# RELAY_5V_3_3V_LEVEL.net
KiCad netlist of a schematic drawn in Altium Designer
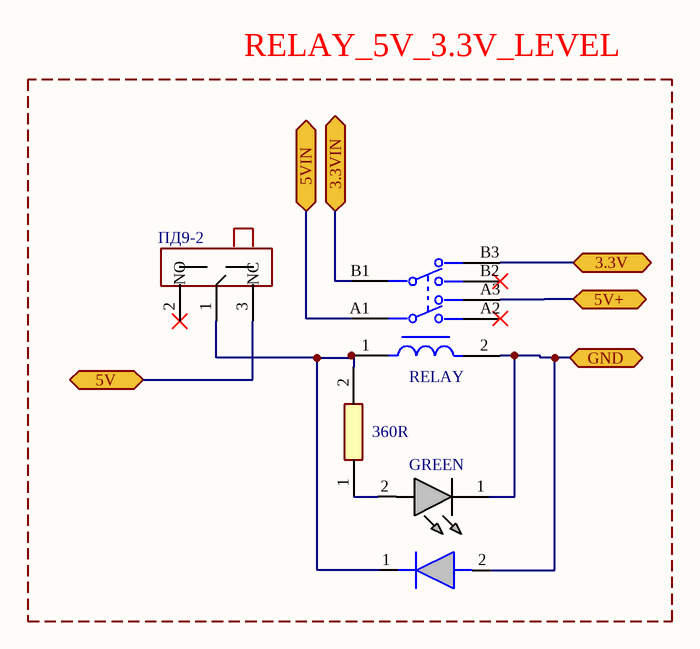
[diagram p0: RELAY_5V_3.3V_LEVEL.SchDoc]

(export (version "E")
  (design (tool "Eeschema 10.0.6"))
  (components
    (comp (ref "DIODRELE2")
      (value "DIOD0805")
      (footprint "DIOD0805")
      (description "1N4448WS-7-F")
      (libsource (lib "Components_Robots") (part "DIOD0805"))
    )
    (comp (ref "LEDRELE2")
      (value "GREEN")
      (footprint "LED0805")
      (description "LED-SMD0805")
      (libsource (lib "Components_Robots") (part "LED0805"))
    )
    (comp (ref "RELAY2")
      (value "RELAY")
      (footprint "RELAY-5V")
      (description "R2G2CH005")
      (libsource (lib "Components_Robots") (part "RELAY-5V"))
    )
    (comp (ref "RES_RELAY_2")
      (value "360R")
      (footprint "RES0805")
      (description "RES-SMD0805")
      (libsource (lib "Components_Robots") (part "RES0805"))
    )
    (comp (ref "ПД9-2RELE1")
      (value "ПД9-2")
      (footprint "ПД9-2")
      (libsource (lib "Components_Robots") (part "ПД9-2"))
    )
  )
  (nets
    (net (code "1") (name "/3.3V") (class "Default")
      (node (ref "RELAY2") (pin "B3") (pinfunction "22_B3") (pintype "passive"))
    )
    (net (code "2") (name "/3.3VIN") (class "Default")
      (node (ref "RELAY2") (pin "B1") (pinfunction "21_B1") (pintype "passive"))
    )
    (net (code "3") (name "/5V") (class "Default")
      (node (ref "ПД9-2RELE1") (pin "3") (pinfunction "NC_3") (pintype "passive"))
    )
    (net (code "4") (name "/5V+") (class "Default")
      (node (ref "RELAY2") (pin "A3") (pinfunction "12_A3") (pintype "passive"))
    )
    (net (code "5") (name "/5VIN") (class "Default")
      (node (ref "RELAY2") (pin "A1") (pinfunction "11_A1") (pintype "passive"))
    )
    (net (code "6") (name "/GND") (class "Default")
      (node (ref "DIODRELE2") (pin "2") (pinfunction "A_2") (pintype "passive"))
      (node (ref "LEDRELE2") (pin "1") (pinfunction "K_1") (pintype "passive"))
      (node (ref "RELAY2") (pin "2") (pinfunction "A2_2") (pintype "passive"))
    )
    (net (code "7") (name "Net-(DIODRELE2-K)") (class "Default")
      (node (ref "DIODRELE2") (pin "1") (pinfunction "K_1") (pintype "passive"))
      (node (ref "RELAY2") (pin "1") (pinfunction "A1_1") (pintype "passive"))
      (node (ref "RES_RELAY_2") (pin "2") (pinfunction "2_2") (pintype "passive"))
      (node (ref "ПД9-2RELE1") (pin "1") (pinfunction "COM_1") (pintype "passive"))
    )
    (net (code "8") (name "Net-(LEDRELE2-A)") (class "Default")
      (node (ref "LEDRELE2") (pin "2") (pinfunction "A_2") (pintype "passive"))
      (node (ref "RES_RELAY_2") (pin "1") (pinfunction "1_1") (pintype "passive"))
    )
    (net (code "9") (name "unconnected-(RELAY2-14-PadA2)") (class "Default")
      (node (ref "RELAY2") (pin "A2") (pinfunction "14_A2") (pintype "passive+no_connect"))
    )
    (net (code "10") (name "unconnected-(RELAY2-24-PadB2)") (class "Default")
      (node (ref "RELAY2") (pin "B2") (pinfunction "24_B2") (pintype "passive+no_connect"))
    )
    (net (code "11") (name "unconnected-(ПД9-2RELE1-NO-Pad2)") (class "Default")
      (node (ref "ПД9-2RELE1") (pin "2") (pinfunction "NO_2") (pintype "passive+no_connect"))
    )
  )
)
